# USB.net
KiCad netlist of a schematic drawn in Altium Designer
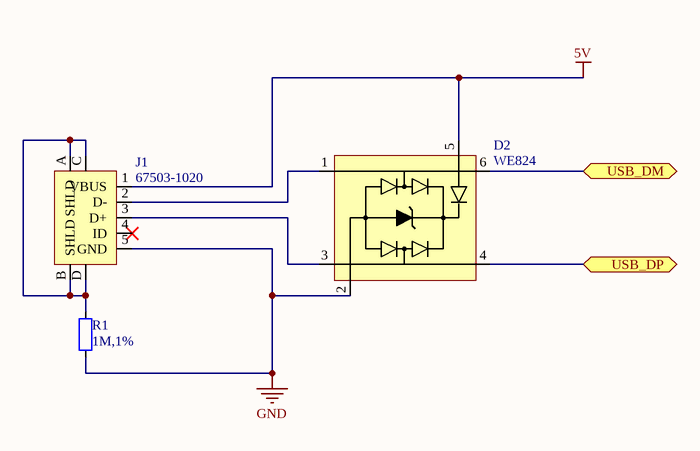
[diagram p0: USB.SchDoc]

(export (version "E")
  (design (tool "Eeschema 10.0.6"))
  (components
    (comp (ref "D2")
      (value "WE824")
      (footprint "SOT95P280X145-6N_SOT23-6")
      (description "TVS DIODE 5VWM 7.7VC SOT23")
      (fields
        (field (name "MANUFACTURER") "Wurth Electronics Inc")
        (field (name "MANUFACTURER PART NUMBER") "82400102")
      )
      (libsource (lib "library") (part "WE824"))
    )
    (comp (ref "J1")
      (value "67503-1020")
      (footprint "MOLEX_0675031020")
      (description "CONN RECEPT MINIUSB R/A 5POS SMD")
      (fields
        (field (name "MANUFACTURER") "Molex Connector Corporation")
        (field (name "MANUFACTURER PART NUMBER") "067503-1020")
      )
      (libsource (lib "library") (part "MOLEX_0675031020"))
    )
    (comp (ref "R1")
      (value "1M,1%")
      (footprint "RESC1608X06N_0603")
      (description "RES 1.00M OHM 1/10W 1% 0603 SMD")
      (fields (field (name "MANUFACTURER") "Yageo") (field (name "POWER") "0.1W"))
      (libsource (lib "library") (part "RESISTOR_1"))
    )
  )
  (nets
    (net (code "1") (name "/USB_DM") (class "Default")
      (node (ref "D2") (pin "6") (pinfunction "6_6") (pintype "passive"))
    )
    (net (code "2") (name "/USB_DP") (class "Default")
      (node (ref "D2") (pin "4") (pinfunction "4_4") (pintype "passive"))
    )
    (net (code "3") (name "5V") (class "Default")
      (node (ref "D2") (pin "5") (pinfunction "5_5") (pintype "passive"))
      (node (ref "J1") (pin "1") (pinfunction "VBUS_1") (pintype "passive"))
    )
    (net (code "4") (name "GND") (class "Default")
      (node (ref "D2") (pin "2") (pinfunction "2_2") (pintype "passive"))
      (node (ref "J1") (pin "5") (pinfunction "GND_5") (pintype "passive"))
      (node (ref "R1") (pin "1") (pinfunction "1_1") (pintype "passive"))
    )
    (net (code "5") (name "Net-(J1-D+)") (class "Default")
      (node (ref "D2") (pin "3") (pinfunction "3_3") (pintype "passive"))
      (node (ref "J1") (pin "3") (pinfunction "D+_3") (pintype "passive"))
    )
    (net (code "6") (name "Net-(J1-D-)") (class "Default")
      (node (ref "D2") (pin "1") (pinfunction "1_1") (pintype "passive"))
      (node (ref "J1") (pin "2") (pinfunction "D-_2") (pintype "passive"))
    )
    (net (code "7") (name "Net-(J1-SHLD-PadA)") (class "Default")
      (node (ref "J1") (pin "A") (pinfunction "SHLD_A") (pintype "passive"))
      (node (ref "J1") (pin "B") (pinfunction "SHLD_B") (pintype "passive"))
      (node (ref "J1") (pin "C") (pinfunction "SHLD_C") (pintype "passive"))
      (node (ref "J1") (pin "D") (pinfunction "SHLD_D") (pintype "passive"))
      (node (ref "R1") (pin "2") (pinfunction "2_2") (pintype "passive"))
    )
    (net (code "8") (name "unconnected-(J1-ID-Pad4)") (class "Default")
      (node (ref "J1") (pin "4") (pinfunction "ID_4") (pintype "passive+no_connect"))
    )
  )
)
